# S2ER11.net
KiCad netlist of a schematic drawn in EAGLE
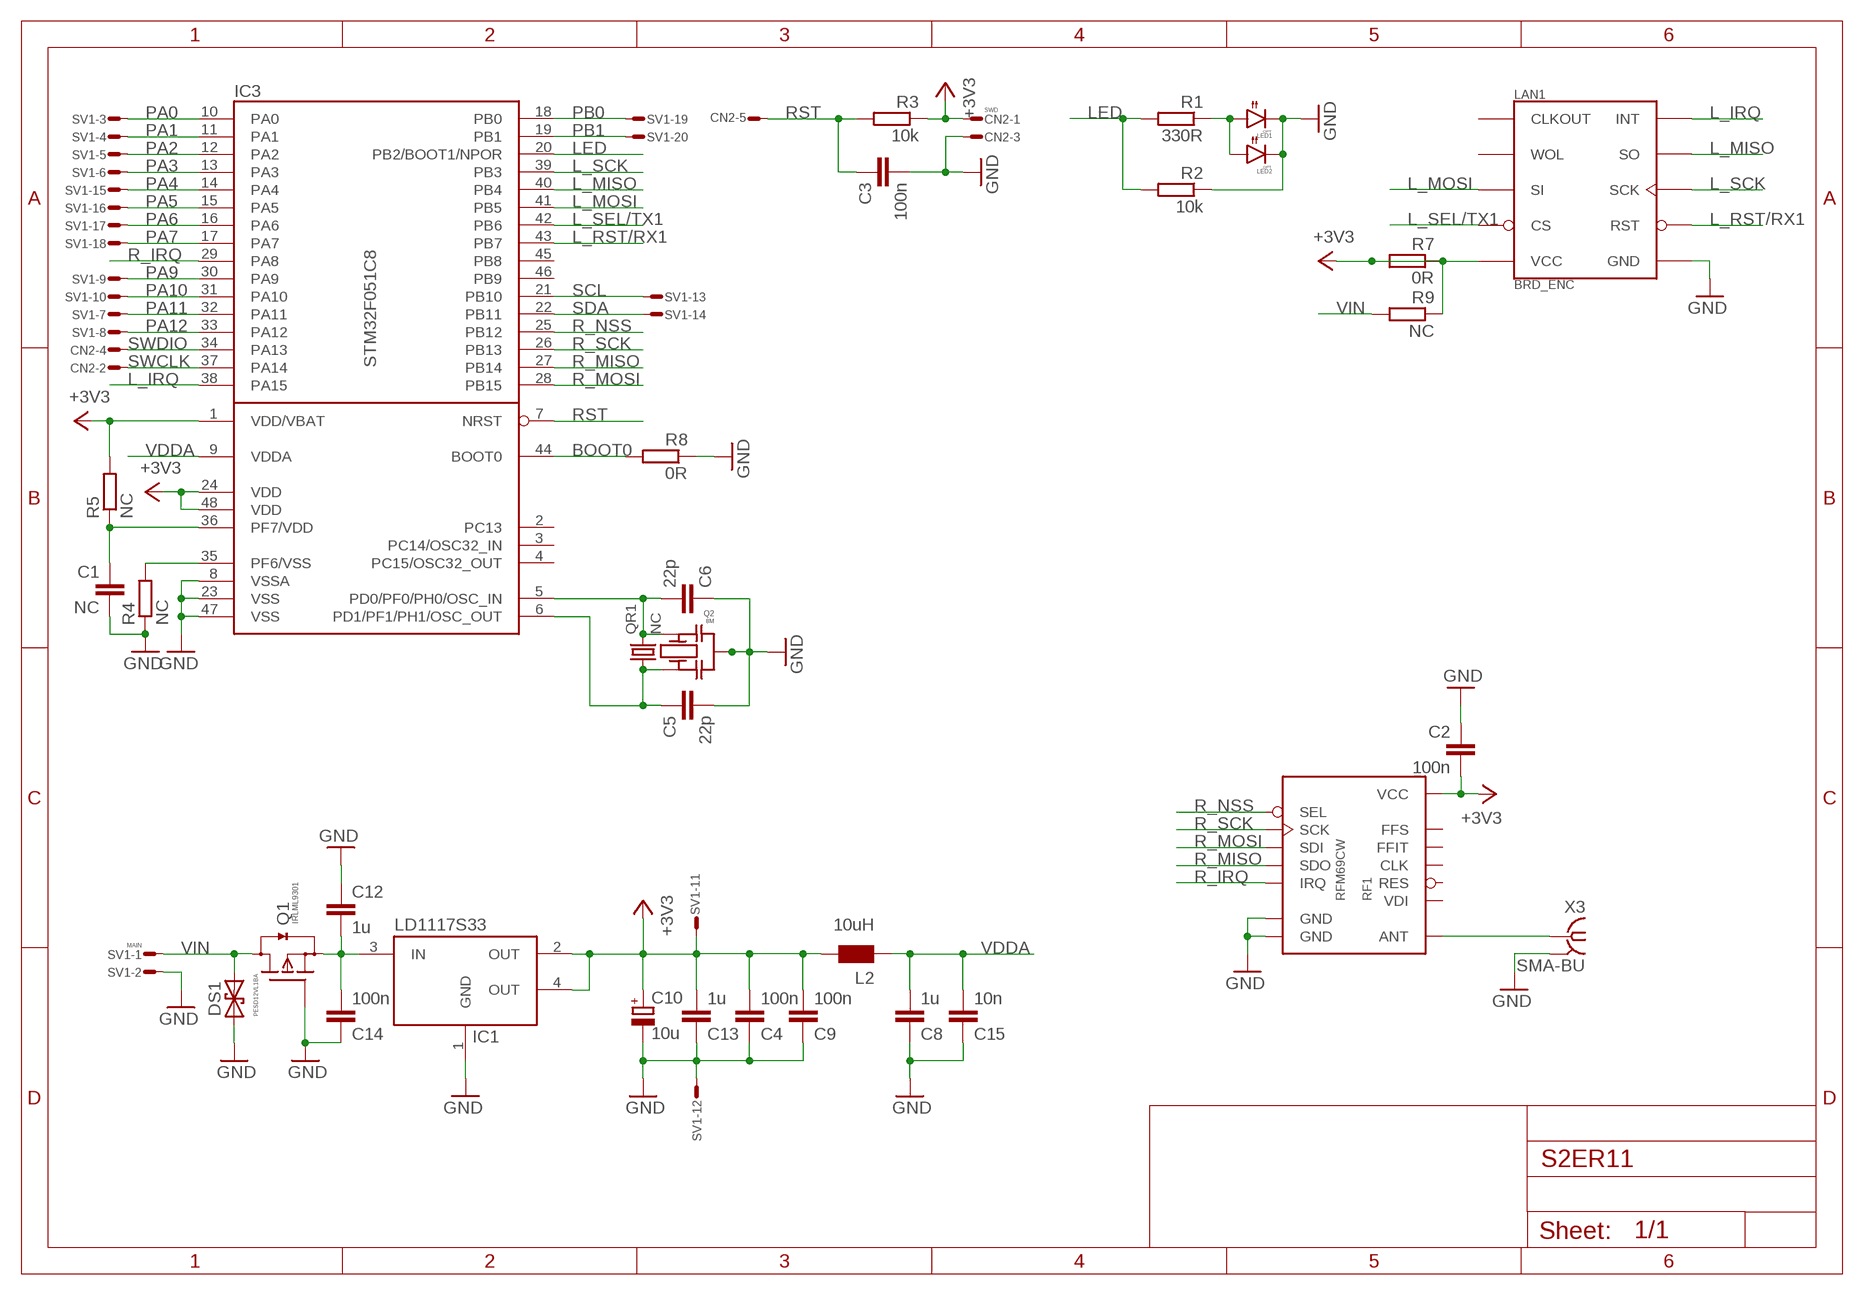
[diagram p0: schematic, sheet 1]

(export (version "E")
  (design (tool "Eeschema 10.0.6"))
  (components
    (comp (ref "C1")
      (value "NC")
      (footprint "eagle-import:0603")
      (libsource (lib "eagle-import") (part "C0603"))
    )
    (comp (ref "C2")
      (value "100n")
      (footprint "eagle-import:0603")
      (libsource (lib "eagle-import") (part "C0603"))
    )
    (comp (ref "C3")
      (value "100n")
      (footprint "eagle-import:0603")
      (libsource (lib "eagle-import") (part "C0603"))
    )
    (comp (ref "C4")
      (value "100n")
      (footprint "eagle-import:0603")
      (libsource (lib "eagle-import") (part "C0603"))
    )
    (comp (ref "C5")
      (value "22p")
      (footprint "eagle-import:0603")
      (libsource (lib "eagle-import") (part "C0603"))
    )
    (comp (ref "C6")
      (value "22p")
      (footprint "eagle-import:0603")
      (libsource (lib "eagle-import") (part "C0603"))
    )
    (comp (ref "C8")
      (value "1u")
      (footprint "eagle-import:0603")
      (libsource (lib "eagle-import") (part "C0603"))
    )
    (comp (ref "C9")
      (value "100n")
      (footprint "eagle-import:0603")
      (libsource (lib "eagle-import") (part "C0603"))
    )
    (comp (ref "C10")
      (value "10u")
      (footprint "eagle-import:SMC_A")
      (libsource (lib "eagle-import") (part "C_POLSMCA"))
    )
    (comp (ref "C12")
      (value "1u")
      (footprint "eagle-import:0603")
      (libsource (lib "eagle-import") (part "C0603"))
    )
    (comp (ref "C13")
      (value "1u")
      (footprint "eagle-import:0603")
      (libsource (lib "eagle-import") (part "C0603"))
    )
    (comp (ref "C14")
      (value "100n")
      (footprint "eagle-import:0603")
      (libsource (lib "eagle-import") (part "C0603"))
    )
    (comp (ref "C15")
      (value "10n")
      (footprint "eagle-import:0603")
      (libsource (lib "eagle-import") (part "C0603"))
    )
    (comp (ref "CN2")
      (value "SWD")
      (footprint "eagle-import:CON6L")
      (libsource (lib "eagle-import") (part "CON6L"))
    )
    (comp (ref "DS1")
      (value "PESD12VL1BA")
      (footprint "eagle-import:SOD323")
      (libsource (lib "eagle-import") (part "TVS-U323"))
    )
    (comp (ref "IC1")
      (value "LD1117S33")
      (footprint "eagle-import:SOT223")
      (libsource (lib "eagle-import") (part "LDO_4P"))
    )
    (comp (ref "IC3")
      (value "STM32F051C8")
      (footprint "eagle-import:LQFP48")
      (libsource (lib "eagle-import") (part "STM32_LQFP48"))
    )
    (comp (ref "L2")
      (value "10uH")
      (footprint "eagle-import:0603")
      (libsource (lib "eagle-import") (part "L0603"))
    )
    (comp (ref "LAN1")
      (value "BRD_ENC")
      (footprint "eagle-import:BRD_ENC")
      (libsource (lib "eagle-import") (part "BRD_ENC"))
    )
    (comp (ref "LED1")
      (value "OPT")
      (footprint "eagle-import:T1-3_4")
      (libsource (lib "eagle-import") (part "LEDT134"))
    )
    (comp (ref "LED2")
      (value "OPT")
      (footprint "eagle-import:1206")
      (libsource (lib "eagle-import") (part "LED1206"))
    )
    (comp (ref "Q1")
      (value "IRLML9301")
      (footprint "eagle-import:SOT23")
      (libsource (lib "eagle-import") (part "FET-PDSOT23"))
    )
    (comp (ref "Q2")
      (value "8M")
      (footprint "eagle-import:CSTCE")
      (libsource (lib "eagle-import") (part "QRCE"))
    )
    (comp (ref "QR1")
      (value "NC")
      (footprint "eagle-import:ABS07")
      (libsource (lib "eagle-import") (part "QABS07"))
    )
    (comp (ref "R1")
      (value "330R")
      (footprint "eagle-import:0603")
      (libsource (lib "eagle-import") (part "R0603"))
    )
    (comp (ref "R2")
      (value "10k")
      (footprint "eagle-import:0603")
      (libsource (lib "eagle-import") (part "R0603"))
    )
    (comp (ref "R3")
      (value "10k")
      (footprint "eagle-import:0603")
      (libsource (lib "eagle-import") (part "R0603"))
    )
    (comp (ref "R4")
      (value "NC")
      (footprint "eagle-import:0402")
      (libsource (lib "eagle-import") (part "R0402"))
    )
    (comp (ref "R5")
      (value "NC")
      (footprint "eagle-import:0402")
      (libsource (lib "eagle-import") (part "R0402"))
    )
    (comp (ref "R7")
      (value "0R")
      (footprint "eagle-import:0603")
      (libsource (lib "eagle-import") (part "R0603"))
    )
    (comp (ref "R8")
      (value "0R")
      (footprint "eagle-import:0402")
      (libsource (lib "eagle-import") (part "R0402"))
    )
    (comp (ref "R9")
      (value "NC")
      (footprint "eagle-import:0603")
      (libsource (lib "eagle-import") (part "R0603"))
    )
    (comp (ref "RF1")
      (value "RFM69CW")
      (footprint "eagle-import:RFM12B")
      (libsource (lib "eagle-import") (part "RFM12BS1-868-"))
    )
    (comp (ref "SV1")
      (value "MAIN")
      (footprint "eagle-import:ML20LS")
      (libsource (lib "eagle-import") (part "ML20?ELS"))
    )
    (comp (ref "X3")
      (value "SMA-BU")
      (footprint "eagle-import:BU-SMA-V")
      (libsource (lib "eagle-import") (part "SMA-BU"))
    )
  )
  (nets
    (net (code "1") (name "+3V3") (class "Default")
      (node (ref "C10") (pin "+") (pinfunction "+_+") (pintype "passive"))
      (node (ref "C13") (pin "2") (pinfunction "2_2") (pintype "passive"))
      (node (ref "C2") (pin "2") (pinfunction "2_2") (pintype "passive"))
      (node (ref "C4") (pin "2") (pinfunction "2_2") (pintype "passive"))
      (node (ref "C9") (pin "2") (pinfunction "2_2") (pintype "passive"))
      (node (ref "CN2") (pin "1") (pinfunction "S_1") (pintype "passive"))
      (node (ref "IC1") (pin "2") (pinfunction "OUT_2") (pintype "bidirectional"))
      (node (ref "IC1") (pin "4") (pinfunction "OUT_4") (pintype "bidirectional"))
      (node (ref "IC3") (pin "1") (pinfunction "VDD/VBAT_1") (pintype "bidirectional"))
      (node (ref "IC3") (pin "24") (pinfunction "VDD_24") (pintype "bidirectional"))
      (node (ref "IC3") (pin "48") (pinfunction "VDD_48") (pintype "bidirectional"))
      (node (ref "L2") (pin "2") (pinfunction "2_2") (pintype "passive"))
      (node (ref "LAN1") (pin "P$9") (pinfunction "VCC_P$9") (pintype "bidirectional"))
      (node (ref "R3") (pin "1") (pinfunction "1_1") (pintype "passive"))
      (node (ref "R5") (pin "2") (pinfunction "2_2") (pintype "passive"))
      (node (ref "R7") (pin "1") (pinfunction "1_1") (pintype "passive"))
      (node (ref "R7") (pin "2") (pinfunction "2_2") (pintype "passive"))
      (node (ref "R9") (pin "1") (pinfunction "1_1") (pintype "passive"))
      (node (ref "RF1") (pin "VDD") (pinfunction "VCC_VDD") (pintype "power_in"))
      (node (ref "SV1") (pin "P$11") (pinfunction "S_P$11") (pintype "passive"))
    )
    (net (code "2") (name "/BOOT0") (class "Default")
      (node (ref "IC3") (pin "44") (pinfunction "BOOT0_44") (pintype "bidirectional"))
      (node (ref "R8") (pin "2") (pinfunction "2_2") (pintype "passive"))
    )
    (net (code "3") (name "/LED") (class "Default")
      (node (ref "IC3") (pin "20") (pinfunction "PB2/BOOT1/NPOR_20") (pintype "bidirectional"))
      (node (ref "R1") (pin "2") (pinfunction "2_2") (pintype "passive"))
      (node (ref "R2") (pin "2") (pinfunction "2_2") (pintype "passive"))
    )
    (net (code "4") (name "/L_IRQ") (class "Default")
      (node (ref "IC3") (pin "38") (pinfunction "PA15_38") (pintype "bidirectional"))
      (node (ref "LAN1") (pin "P$2") (pinfunction "INT_P$2") (pintype "open_collector"))
    )
    (net (code "5") (name "/L_MISO") (class "Default")
      (node (ref "IC3") (pin "40") (pinfunction "PB4_40") (pintype "bidirectional"))
      (node (ref "LAN1") (pin "P$4") (pinfunction "SO_P$4") (pintype "output"))
    )
    (net (code "6") (name "/L_MOSI") (class "Default")
      (node (ref "IC3") (pin "41") (pinfunction "PB5_41") (pintype "bidirectional"))
      (node (ref "LAN1") (pin "P$5") (pinfunction "SI_P$5") (pintype "input"))
    )
    (net (code "7") (name "/L_RST{slash}RX1") (class "Default")
      (node (ref "IC3") (pin "43") (pinfunction "PB7_43") (pintype "bidirectional"))
      (node (ref "LAN1") (pin "P$8") (pinfunction "RST_P$8") (pintype "bidirectional"))
    )
    (net (code "8") (name "/L_SCK") (class "Default")
      (node (ref "IC3") (pin "39") (pinfunction "PB3_39") (pintype "bidirectional"))
      (node (ref "LAN1") (pin "P$6") (pinfunction "SCK_P$6") (pintype "input"))
    )
    (net (code "9") (name "/L_SEL{slash}TX1") (class "Default")
      (node (ref "IC3") (pin "42") (pinfunction "PB6_42") (pintype "bidirectional"))
      (node (ref "LAN1") (pin "P$7") (pinfunction "CS_P$7") (pintype "input"))
    )
    (net (code "10") (name "/PA0") (class "Default")
      (node (ref "IC3") (pin "10") (pinfunction "PA0_10") (pintype "bidirectional"))
      (node (ref "SV1") (pin "P$3") (pinfunction "S_P$3") (pintype "passive"))
    )
    (net (code "11") (name "/PA1") (class "Default")
      (node (ref "IC3") (pin "11") (pinfunction "PA1_11") (pintype "bidirectional"))
      (node (ref "SV1") (pin "P$4") (pinfunction "S_P$4") (pintype "passive"))
    )
    (net (code "12") (name "/PA2") (class "Default")
      (node (ref "IC3") (pin "12") (pinfunction "PA2_12") (pintype "bidirectional"))
      (node (ref "SV1") (pin "P$5") (pinfunction "S_P$5") (pintype "passive"))
    )
    (net (code "13") (name "/PA3") (class "Default")
      (node (ref "IC3") (pin "13") (pinfunction "PA3_13") (pintype "bidirectional"))
      (node (ref "SV1") (pin "P$6") (pinfunction "S_P$6") (pintype "passive"))
    )
    (net (code "14") (name "/PA4") (class "Default")
      (node (ref "IC3") (pin "14") (pinfunction "PA4_14") (pintype "bidirectional"))
      (node (ref "SV1") (pin "P$15") (pinfunction "S_P$15") (pintype "passive"))
    )
    (net (code "15") (name "/PA5") (class "Default")
      (node (ref "IC3") (pin "15") (pinfunction "PA5_15") (pintype "bidirectional"))
      (node (ref "SV1") (pin "P$16") (pinfunction "S_P$16") (pintype "passive"))
    )
    (net (code "16") (name "/PA6") (class "Default")
      (node (ref "IC3") (pin "16") (pinfunction "PA6_16") (pintype "bidirectional"))
      (node (ref "SV1") (pin "P$17") (pinfunction "S_P$17") (pintype "passive"))
    )
    (net (code "17") (name "/PA7") (class "Default")
      (node (ref "IC3") (pin "17") (pinfunction "PA7_17") (pintype "bidirectional"))
      (node (ref "SV1") (pin "P$18") (pinfunction "S_P$18") (pintype "passive"))
    )
    (net (code "18") (name "/PA9") (class "Default")
      (node (ref "IC3") (pin "30") (pinfunction "PA9_30") (pintype "bidirectional"))
      (node (ref "SV1") (pin "P$9") (pinfunction "S_P$9") (pintype "passive"))
    )
    (net (code "19") (name "/PA10") (class "Default")
      (node (ref "IC3") (pin "31") (pinfunction "PA10_31") (pintype "bidirectional"))
      (node (ref "SV1") (pin "P$10") (pinfunction "S_P$10") (pintype "passive"))
    )
    (net (code "20") (name "/PA11") (class "Default")
      (node (ref "IC3") (pin "32") (pinfunction "PA11_32") (pintype "bidirectional"))
      (node (ref "SV1") (pin "P$7") (pinfunction "S_P$7") (pintype "passive"))
    )
    (net (code "21") (name "/PA12") (class "Default")
      (node (ref "IC3") (pin "33") (pinfunction "PA12_33") (pintype "bidirectional"))
      (node (ref "SV1") (pin "P$8") (pinfunction "S_P$8") (pintype "passive"))
    )
    (net (code "22") (name "/PB0") (class "Default")
      (node (ref "IC3") (pin "18") (pinfunction "PB0_18") (pintype "bidirectional"))
      (node (ref "SV1") (pin "P$19") (pinfunction "S_P$19") (pintype "passive"))
    )
    (net (code "23") (name "/PB1") (class "Default")
      (node (ref "IC3") (pin "19") (pinfunction "PB1_19") (pintype "bidirectional"))
      (node (ref "SV1") (pin "P$20") (pinfunction "S_P$20") (pintype "passive"))
    )
    (net (code "24") (name "/RST") (class "Default")
      (node (ref "C3") (pin "1") (pinfunction "1_1") (pintype "passive"))
      (node (ref "CN2") (pin "5") (pinfunction "S_5") (pintype "passive"))
      (node (ref "IC3") (pin "7") (pinfunction "NRST_7") (pintype "bidirectional"))
      (node (ref "R3") (pin "2") (pinfunction "2_2") (pintype "passive"))
    )
    (net (code "25") (name "/R_IRQ") (class "Default")
      (node (ref "IC3") (pin "29") (pinfunction "PA8_29") (pintype "bidirectional"))
      (node (ref "RF1") (pin "IRQ") (pinfunction "IRQ_IRQ") (pintype "open_collector"))
    )
    (net (code "26") (name "/R_MISO") (class "Default")
      (node (ref "IC3") (pin "27") (pinfunction "PB14_27") (pintype "bidirectional"))
      (node (ref "RF1") (pin "SDO") (pinfunction "SDO_SDO") (pintype "output"))
    )
    (net (code "27") (name "/R_MOSI") (class "Default")
      (node (ref "IC3") (pin "28") (pinfunction "PB15_28") (pintype "bidirectional"))
      (node (ref "RF1") (pin "SDI") (pinfunction "SDI_SDI") (pintype "input"))
    )
    (net (code "28") (name "/R_NSS") (class "Default")
      (node (ref "IC3") (pin "25") (pinfunction "PB12_25") (pintype "bidirectional"))
      (node (ref "RF1") (pin "SEL") (pinfunction "SEL_SEL") (pintype "input"))
    )
    (net (code "29") (name "/R_SCK") (class "Default")
      (node (ref "IC3") (pin "26") (pinfunction "PB13_26") (pintype "bidirectional"))
      (node (ref "RF1") (pin "SCK") (pinfunction "SCK_SCK") (pintype "input"))
    )
    (net (code "30") (name "/SCL") (class "Default")
      (node (ref "IC3") (pin "21") (pinfunction "PB10_21") (pintype "bidirectional"))
      (node (ref "SV1") (pin "P$13") (pinfunction "S_P$13") (pintype "passive"))
    )
    (net (code "31") (name "/SDA") (class "Default")
      (node (ref "IC3") (pin "22") (pinfunction "PB11_22") (pintype "bidirectional"))
      (node (ref "SV1") (pin "P$14") (pinfunction "S_P$14") (pintype "passive"))
    )
    (net (code "32") (name "/SWCLK") (class "Default")
      (node (ref "CN2") (pin "2") (pinfunction "S_2") (pintype "passive"))
      (node (ref "IC3") (pin "37") (pinfunction "PA14_37") (pintype "bidirectional"))
    )
    (net (code "33") (name "/SWDIO") (class "Default")
      (node (ref "CN2") (pin "4") (pinfunction "S_4") (pintype "passive"))
      (node (ref "IC3") (pin "34") (pinfunction "PA13_34") (pintype "bidirectional"))
    )
    (net (code "34") (name "/VDDA") (class "Default")
      (node (ref "C15") (pin "2") (pinfunction "2_2") (pintype "passive"))
      (node (ref "C8") (pin "2") (pinfunction "2_2") (pintype "passive"))
      (node (ref "IC3") (pin "9") (pinfunction "VDDA_9") (pintype "bidirectional"))
      (node (ref "L2") (pin "1") (pinfunction "1_1") (pintype "passive"))
    )
    (net (code "35") (name "/VIN") (class "Default")
      (node (ref "DS1") (pin "C") (pinfunction "2_C") (pintype "passive"))
      (node (ref "Q1") (pin "3") (pinfunction "D_3") (pintype "passive"))
      (node (ref "R9") (pin "2") (pinfunction "2_2") (pintype "passive"))
      (node (ref "SV1") (pin "P$1") (pinfunction "S_P$1") (pintype "passive"))
    )
    (net (code "36") (name "GND") (class "Default")
      (node (ref "C1") (pin "2") (pinfunction "2_2") (pintype "passive"))
      (node (ref "C10") (pin "-") (pinfunction "-_-") (pintype "passive"))
      (node (ref "C12") (pin "1") (pinfunction "1_1") (pintype "passive"))
      (node (ref "C13") (pin "1") (pinfunction "1_1") (pintype "passive"))
      (node (ref "C14") (pin "1") (pinfunction "1_1") (pintype "passive"))
      (node (ref "C15") (pin "1") (pinfunction "1_1") (pintype "passive"))
      (node (ref "C2") (pin "1") (pinfunction "1_1") (pintype "passive"))
      (node (ref "C3") (pin "2") (pinfunction "2_2") (pintype "passive"))
      (node (ref "C4") (pin "1") (pinfunction "1_1") (pintype "passive"))
      (node (ref "C5") (pin "2") (pinfunction "2_2") (pintype "passive"))
      (node (ref "C6") (pin "1") (pinfunction "1_1") (pintype "passive"))
      (node (ref "C8") (pin "1") (pinfunction "1_1") (pintype "passive"))
      (node (ref "C9") (pin "1") (pinfunction "1_1") (pintype "passive"))
      (node (ref "CN2") (pin "3") (pinfunction "S_3") (pintype "passive"))
      (node (ref "DS1") (pin "A") (pinfunction "1_A") (pintype "passive"))
      (node (ref "IC1") (pin "1") (pinfunction "GND_1") (pintype "bidirectional"))
      (node (ref "IC3") (pin "23") (pinfunction "VSS_23") (pintype "bidirectional"))
      (node (ref "IC3") (pin "47") (pinfunction "VSS_47") (pintype "bidirectional"))
      (node (ref "IC3") (pin "8") (pinfunction "VSSA_8") (pintype "bidirectional"))
      (node (ref "LAN1") (pin "P$10") (pinfunction "GND_P$10") (pintype "bidirectional"))
      (node (ref "LED1") (pin "C") (pinfunction "C_C") (pintype "bidirectional"))
      (node (ref "LED2") (pin "2") (pinfunction "C_2") (pintype "bidirectional"))
      (node (ref "Q1") (pin "1") (pinfunction "G_1") (pintype "passive"))
      (node (ref "Q2") (pin "G") (pinfunction "M_G") (pintype "passive"))
      (node (ref "R2") (pin "1") (pinfunction "1_1") (pintype "passive"))
      (node (ref "R4") (pin "1") (pinfunction "1_1") (pintype "passive"))
      (node (ref "R8") (pin "1") (pinfunction "1_1") (pintype "passive"))
      (node (ref "RF1") (pin "GND") (pinfunction "GND_GND") (pintype "power_in"))
      (node (ref "RF1") (pin "GND@1") (pinfunction "GND_GND@1") (pintype "power_in"))
      (node (ref "SV1") (pin "P$12") (pinfunction "S_P$12") (pintype "passive"))
      (node (ref "SV1") (pin "P$2") (pinfunction "S_P$2") (pintype "passive"))
      (node (ref "X3") (pin "2") (pinfunction "2_2") (pintype "passive"))
      (node (ref "X3") (pin "3") (pinfunction "2_3") (pintype "passive"))
      (node (ref "X3") (pin "4") (pinfunction "2_4") (pintype "passive"))
      (node (ref "X3") (pin "5") (pinfunction "2_5") (pintype "passive"))
    )
    (net (code "37") (name "Net-(IC1-IN)") (class "Default")
      (node (ref "C12") (pin "2") (pinfunction "2_2") (pintype "passive"))
      (node (ref "C14") (pin "2") (pinfunction "2_2") (pintype "passive"))
      (node (ref "IC1") (pin "3") (pinfunction "IN_3") (pintype "bidirectional"))
      (node (ref "Q1") (pin "2") (pinfunction "S_2") (pintype "passive"))
    )
    (net (code "38") (name "Net-(IC3-PD0{slash}PF0{slash}PH0{slash}OSC_IN)") (class "Default")
      (node (ref "C6") (pin "2") (pinfunction "2_2") (pintype "passive"))
      (node (ref "IC3") (pin "5") (pinfunction "PD0/PF0/PH0/OSC_IN_5") (pintype "bidirectional"))
      (node (ref "Q2") (pin "A") (pinfunction "1_A") (pintype "passive"))
      (node (ref "QR1") (pin "P$2") (pinfunction "2_P$2") (pintype "passive"))
    )
    (net (code "39") (name "Net-(IC3-PD1{slash}PF1{slash}PH1{slash}OSC_OUT)") (class "Default")
      (node (ref "C5") (pin "1") (pinfunction "1_1") (pintype "passive"))
      (node (ref "IC3") (pin "6") (pinfunction "PD1/PF1/PH1/OSC_OUT_6") (pintype "bidirectional"))
      (node (ref "Q2") (pin "B") (pinfunction "2_B") (pintype "passive"))
      (node (ref "QR1") (pin "P$1") (pinfunction "1_P$1") (pintype "passive"))
    )
    (net (code "40") (name "Net-(IC3-PF6{slash}VSS)") (class "Default")
      (node (ref "IC3") (pin "35") (pinfunction "PF6/VSS_35") (pintype "bidirectional"))
      (node (ref "R4") (pin "2") (pinfunction "2_2") (pintype "passive"))
    )
    (net (code "41") (name "Net-(IC3-PF7{slash}VDD)") (class "Default")
      (node (ref "C1") (pin "1") (pinfunction "1_1") (pintype "passive"))
      (node (ref "IC3") (pin "36") (pinfunction "PF7/VDD_36") (pintype "bidirectional"))
      (node (ref "R5") (pin "1") (pinfunction "1_1") (pintype "passive"))
    )
    (net (code "42") (name "Net-(LED2-A)") (class "Default")
      (node (ref "LED1") (pin "A") (pinfunction "A_A") (pintype "bidirectional"))
      (node (ref "LED2") (pin "1") (pinfunction "A_1") (pintype "bidirectional"))
      (node (ref "R1") (pin "1") (pinfunction "1_1") (pintype "passive"))
    )
    (net (code "43") (name "Net-(RF1-PadANT)") (class "Default")
      (node (ref "RF1") (pin "ANT") (pinfunction "ANT_ANT") (pintype "passive"))
      (node (ref "X3") (pin "1") (pinfunction "1_1") (pintype "passive"))
    )
    (net (code "44") (name "unconnected-(IC3-PB8-Pad45)") (class "Default")
      (node (ref "IC3") (pin "45") (pinfunction "PB8_45") (pintype "bidirectional"))
    )
    (net (code "45") (name "unconnected-(IC3-PB9-Pad46)") (class "Default")
      (node (ref "IC3") (pin "46") (pinfunction "PB9_46") (pintype "bidirectional"))
    )
    (net (code "46") (name "unconnected-(IC3-PC13-Pad2)") (class "Default")
      (node (ref "IC3") (pin "2") (pinfunction "PC13_2") (pintype "bidirectional"))
    )
    (net (code "47") (name "unconnected-(IC3-PC14{slash}OSC32_IN-Pad3)") (class "Default")
      (node (ref "IC3") (pin "3") (pinfunction "PC14/OSC32_IN_3") (pintype "bidirectional"))
    )
    (net (code "48") (name "unconnected-(IC3-PC15{slash}OSC32_OUT-Pad4)") (class "Default")
      (node (ref "IC3") (pin "4") (pinfunction "PC15/OSC32_OUT_4") (pintype "bidirectional"))
    )
    (net (code "49") (name "unconnected-(LAN1-CLKOUT-PadP$1)") (class "Default")
      (node (ref "LAN1") (pin "P$1") (pinfunction "CLKOUT_P$1") (pintype "output"))
    )
    (net (code "50") (name "unconnected-(LAN1-WOL-PadP$3)") (class "Default")
      (node (ref "LAN1") (pin "P$3") (pinfunction "WOL_P$3") (pintype "output"))
    )
    (net (code "51") (name "unconnected-(RF1-FFIT-PadCFIL)") (class "Default")
      (node (ref "RF1") (pin "CFIL") (pinfunction "FFIT_CFIL") (pintype "bidirectional"))
    )
    (net (code "52") (name "unconnected-(RF1-PadCLK)") (class "Default")
      (node (ref "RF1") (pin "CLK") (pinfunction "CLK_CLK") (pintype "output"))
    )
    (net (code "53") (name "unconnected-(RF1-PadFFS)") (class "Default")
      (node (ref "RF1") (pin "FFS") (pinfunction "FFS_FFS") (pintype "bidirectional"))
    )
    (net (code "54") (name "unconnected-(RF1-RES-Pad{slash}RES)") (class "Default")
      (node (ref "RF1") (pin "/RES") (pinfunction "RES_/RES") (pintype "bidirectional"))
    )
    (net (code "55") (name "unconnected-(RF1-VDI-PadINT)") (class "Default")
      (node (ref "RF1") (pin "INT") (pinfunction "VDI_INT") (pintype "bidirectional"))
    )
  )
)
